# trace_4.net
KiCad netlist of a schematic drawn in Altium Designer
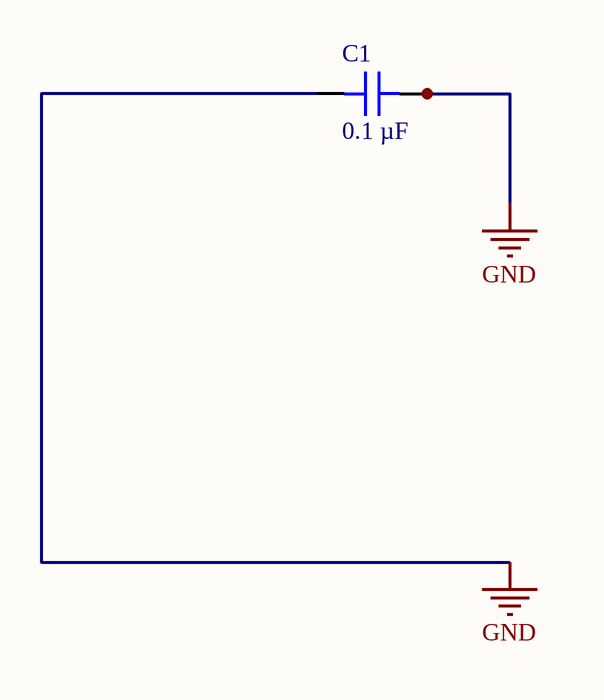
[diagram p0: trace_4.SchDoc]

(export (version "E")
  (design (tool "Eeschema 10.0.6"))
  (components
    (comp (ref "C1")
      (value "0.1 µF")
      (footprint "CAP 01005_0402")
      (description "CAP CER 0.1UF 6.3V X5R 01005")
      (fields
        (field (name "PART NUMBER") "CL02A104KQ2NNNC")
        (field (name "MANUFACTURER") "Samsung Electro-Mechanics")
      )
      (libsource (lib "Celestial Altium Library - altium_library") (part "Capacitor"))
    )
  )
  (nets
    (net (code "1") (name "GND") (class "Default")
      (node (ref "C1") (pin "1") (pinfunction "1_1") (pintype "passive"))
      (node (ref "C1") (pin "2") (pinfunction "2_2") (pintype "passive"))
    )
  )
)
